# cpu.net
KiCad netlist of a schematic drawn in Altium Designer
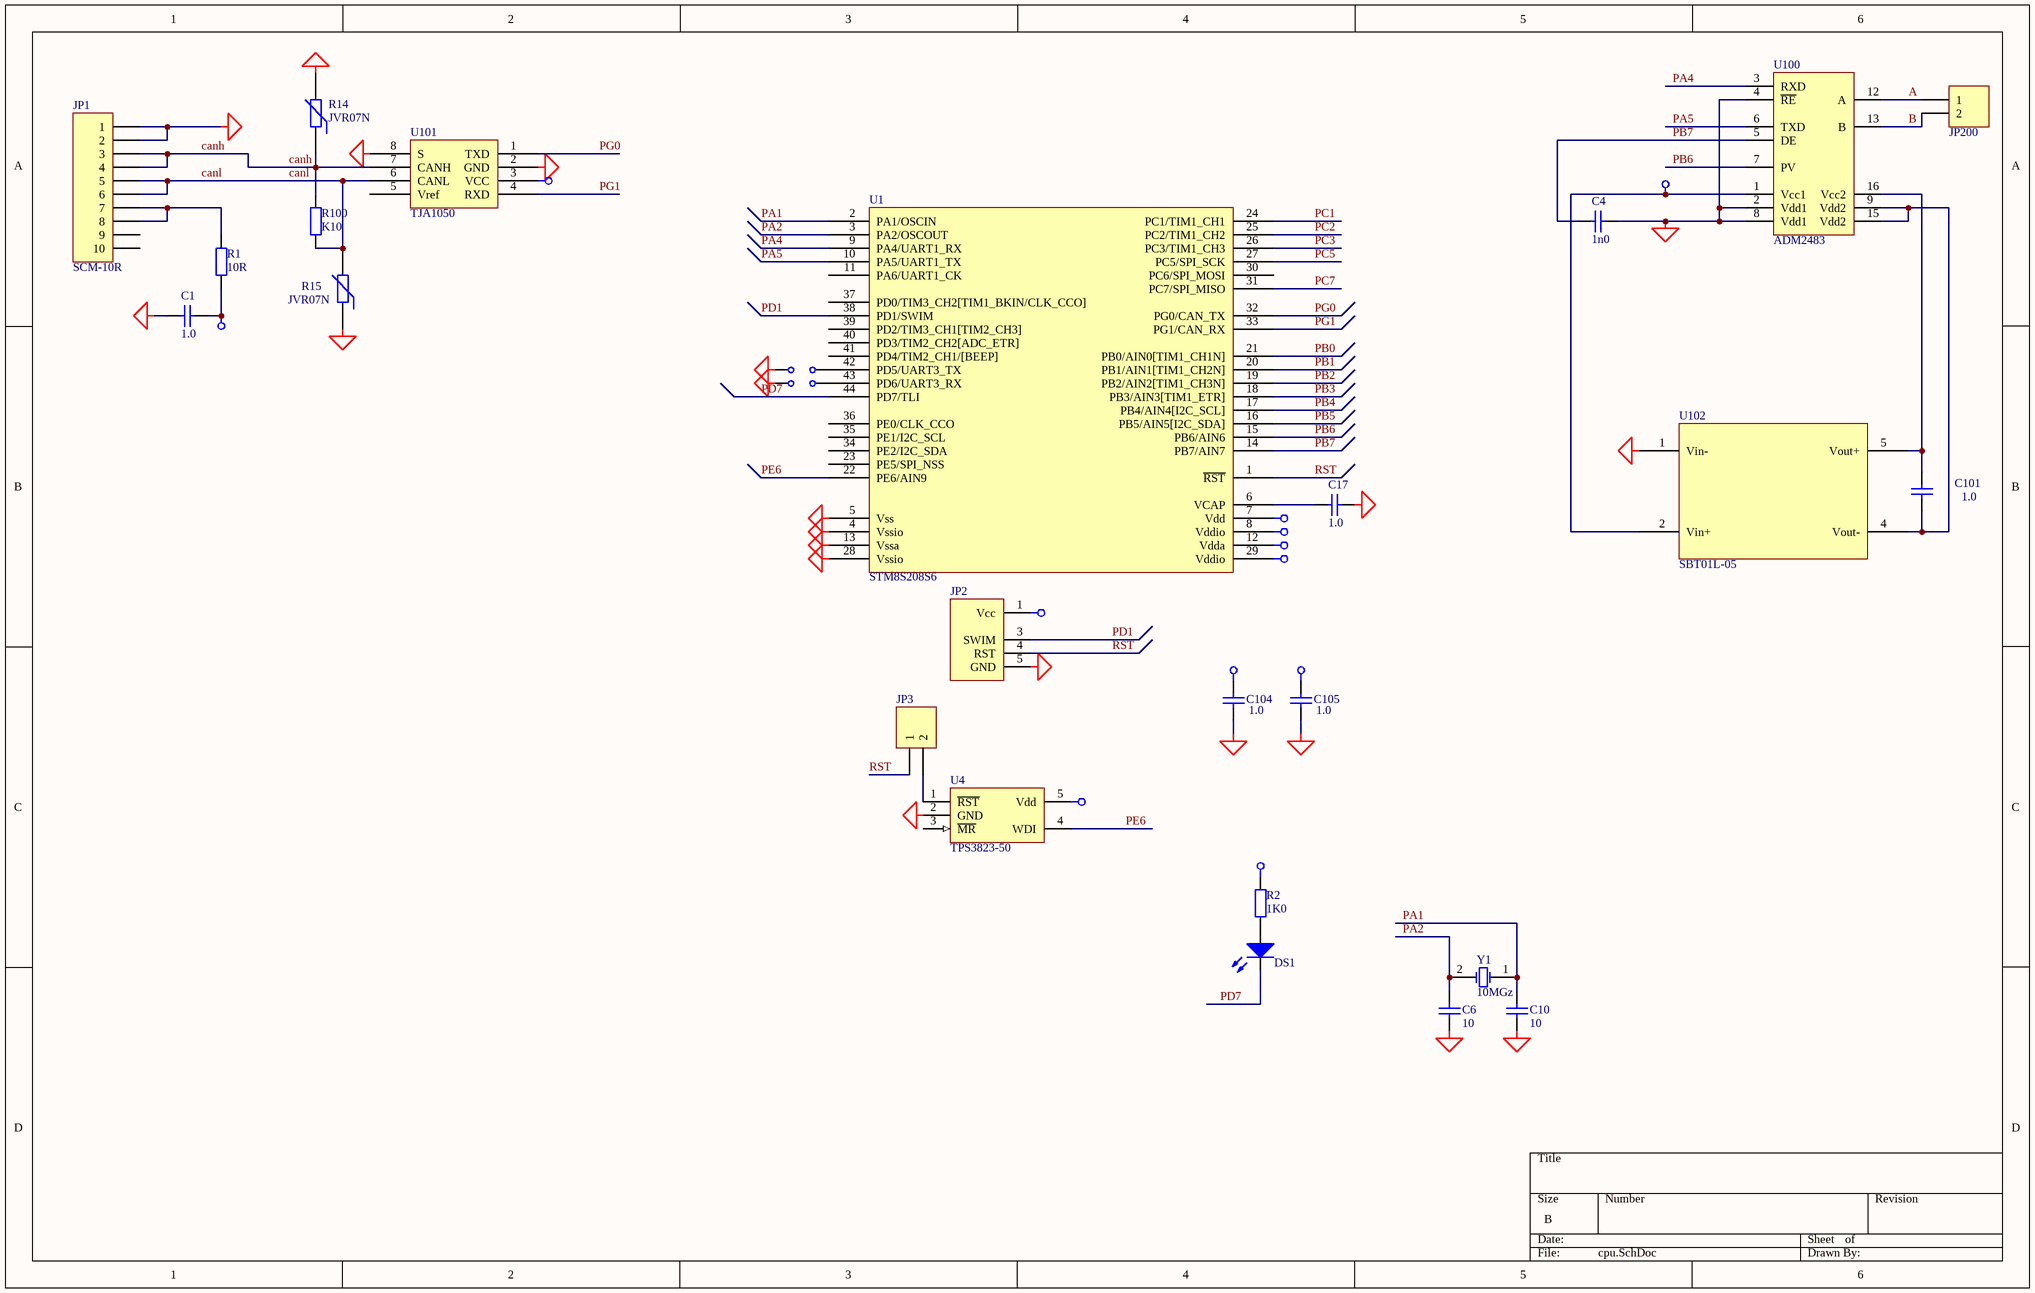
[diagram p0: cpu.SchDoc]

(export (version "E")
  (design (tool "Eeschema 10.0.6"))
  (components
    (comp (ref "C1")
      (value "1.0")
      (footprint "_1206")
      (description "Capacitor")
      (fields (field (name "MANUFACTURER") "Generic Components") (field (name "PUBLISHER") "Altium Limited"))
      (libsource (lib "BUF") (part "Cap"))
    )
    (comp (ref "C4")
      (value "1n0")
      (footprint "_1206")
      (description "Capacitor (Semiconductor SIM Model)")
      (fields (field (name "MANUFACTURER") "Generic Components") (field (name "PUBLISHER") "Altium Limited"))
      (libsource (lib "Miscellaneous Devices") (part "Cap Semi"))
    )
    (comp (ref "C6")
      (value "10")
      (footprint "_1206")
      (description "Capacitor (Semiconductor SIM Model)")
      (fields (field (name "MANUFACTURER") "Generic Components") (field (name "PUBLISHER") "Altium Limited"))
      (libsource (lib "Miscellaneous Devices") (part "Cap Semi"))
    )
    (comp (ref "C10")
      (value "10")
      (footprint "_1206")
      (description "Capacitor (Semiconductor SIM Model)")
      (fields (field (name "MANUFACTURER") "Generic Components") (field (name "PUBLISHER") "Altium Limited"))
      (libsource (lib "Miscellaneous Devices") (part "Cap Semi"))
    )
    (comp (ref "C17")
      (value "1.0")
      (footprint "_1206")
      (description "Capacitor (Semiconductor SIM Model)")
      (fields (field (name "MANUFACTURER") "Generic Components") (field (name "PUBLISHER") "Altium Limited"))
      (libsource (lib "Miscellaneous Devices") (part "Cap Semi"))
    )
    (comp (ref "C101")
      (value "1.0")
      (footprint "_1206")
      (description "Capacitor (Semiconductor SIM Model)")
      (fields (field (name "MANUFACTURER") "Generic Components") (field (name "PUBLISHER") "Altium Limited"))
      (libsource (lib "Miscellaneous Devices") (part "Cap Semi"))
    )
    (comp (ref "C104")
      (value "1.0")
      (footprint "_1206")
      (description "Capacitor")
      (fields (field (name "MANUFACTURER") "Generic Components") (field (name "PUBLISHER") "Altium Limited"))
      (libsource (lib "BUF") (part "Cap"))
    )
    (comp (ref "C105")
      (value "1.0")
      (footprint "_1206")
      (description "Capacitor")
      (fields (field (name "MANUFACTURER") "Generic Components") (field (name "PUBLISHER") "Altium Limited"))
      (libsource (lib "BUF") (part "Cap"))
    )
    (comp (ref "DS1")
      (value "LED0")
      (footprint "el3")
      (description "Typical INFRARED GaAs LED")
      (fields (field (name "MANUFACTURER") "Generic Components") (field (name "PUBLISHER") "Altium Limited"))
      (libsource (lib "PAL") (part "LED0"))
    )
    (comp (ref "J1")
      (value "PLS2")
      (footprint "jmp")
      (description "Switch")
      (fields (field (name "MANUFACTURER") "Generic Components") (field (name "PUBLISHER") "Altium Limited"))
      (libsource (lib "PAL") (part "JMP"))
    )
    (comp (ref "J2")
      (value "PLS2")
      (footprint "jmp")
      (description "Switch")
      (fields (field (name "MANUFACTURER") "Generic Components") (field (name "PUBLISHER") "Altium Limited"))
      (libsource (lib "PAL") (part "JMP"))
    )
    (comp (ref "JP1")
      (value "SCM-10R")
      (footprint "HDR2X5")
      (description "Header, 10-Pin")
      (fields (field (name "MANUFACTURER") "Generic Components") (field (name "PUBLISHER") "Altium Limited"))
      (libsource (lib "Miscellaneous Connectors") (part "MHDR1X10"))
    )
    (comp (ref "JP2") (value "~") (footprint "HDR1X5_uart") (libsource (lib "PAL") (part "SWIM_CONN")))
    (comp (ref "JP3")
      (value "~")
      (footprint "HDR1X2")
      (description "Header, 2-Pin")
      (fields (field (name "MANUFACTURER") "Generic Components") (field (name "PUBLISHER") "Altium Limited"))
      (libsource (lib "Miscellaneous Connectors") (part "Header 2"))
    )
    (comp (ref "JP200")
      (value "15EDGR-3.5-2P")
      (footprint "2EDGR-3.5-2P")
      (description "Header, 2-Pin")
      (fields (field (name "MANUFACTURER") "Generic Components") (field (name "PUBLISHER") "Altium Limited"))
      (libsource (lib "Miscellaneous Connectors") (part "MHDR1X2"))
    )
    (comp (ref "R1")
      (value "10R")
      (footprint "_1206")
      (description "Resistor")
      (fields (field (name "MANUFACTURER") "Generic Components") (field (name "PUBLISHER") "Altium Limited"))
      (libsource (lib "Miscellaneous Devices") (part "Res2"))
    )
    (comp (ref "R2")
      (value "1K0")
      (footprint "_1206")
      (description "Resistor")
      (fields (field (name "MANUFACTURER") "Generic Components") (field (name "PUBLISHER") "Altium Limited"))
      (libsource (lib "") (part "Res2_1"))
    )
    (comp (ref "R14")
      (value "JVR07N")
      (footprint "JVR07N")
      (description "Varistor (Voltage-Sensitive Resistor)")
      (fields (field (name "MANUFACTURER") "Generic Components") (field (name "PUBLISHER") "Altium Limited"))
      (libsource (lib "Miscellaneous Devices") (part "Res Varistor"))
    )
    (comp (ref "R15")
      (value "JVR07N")
      (footprint "JVR07N")
      (description "Varistor (Voltage-Sensitive Resistor)")
      (fields (field (name "MANUFACTURER") "Generic Components") (field (name "PUBLISHER") "Altium Limited"))
      (libsource (lib "Miscellaneous Devices") (part "Res Varistor"))
    )
    (comp (ref "R100")
      (value "K10")
      (footprint "_1206")
      (description "Resistor")
      (fields (field (name "MANUFACTURER") "Generic Components") (field (name "PUBLISHER") "Altium Limited"))
      (libsource (lib "Miscellaneous Devices") (part "Res2"))
    )
    (comp (ref "U1")
      (value "STM8S208S6")
      (footprint "QFP10X10-G44/G10N")
      (libsource (lib "PAL") (part "STM8S208S6"))
    )
    (comp (ref "U4")
      (value "TPS3823-50")
      (footprint "SO-G5/P.95")
      (description "Reset IC")
      (fields
        (field (name "MANUFACTURER") "National Semiconductor")
        (field (name "PUBLISHER") "Altium Limited")
      )
      (libsource (lib "PAL") (part "TPS3823"))
    )
    (comp (ref "U100") (value "ADM2483") (footprint "SO-G16/D10.4") (libsource (lib "PAL") (part "ADM2483")))
    (comp (ref "U101") (value "TJA1050") (footprint "SO-G8/D5") (libsource (lib "PAL") (part "TJA1050")))
    (comp (ref "U102") (value "SBT01L-05") (footprint "SBT01L") (libsource (lib "PAL") (part "SBT01L")))
    (comp (ref "Y1")
      (value "10MGz")
      (footprint "QWARZ1")
      (description "Crystal Oscillator")
      (fields (field (name "MANUFACTURER") "Generic Components") (field (name "PUBLISHER") "Altium Limited"))
      (libsource (lib "Miscellaneous Devices") (part "XTAL"))
    )
  )
  (nets
    (net (code "1") (name "+5v") (class "Default")
      (node (ref "C1") (pin "2") (pinfunction "2_2") (pintype "passive"))
      (node (ref "C104") (pin "2") (pinfunction "2_2") (pintype "passive"))
      (node (ref "C105") (pin "2") (pinfunction "2_2") (pintype "passive"))
      (node (ref "JP2") (pin "1") (pinfunction "Vcc_1") (pintype "passive"))
      (node (ref "R1") (pin "1") (pinfunction "1_1") (pintype "passive"))
      (node (ref "R2") (pin "1") (pinfunction "1_1") (pintype "passive"))
      (node (ref "U1") (pin "29") (pinfunction "Vddio_29") (pintype "passive"))
      (node (ref "U1") (pin "7") (pinfunction "Vdd_7") (pintype "passive"))
      (node (ref "U1") (pin "8") (pinfunction "Vddio_8") (pintype "passive"))
      (node (ref "U100") (pin "1") (pinfunction "Vcc1_1") (pintype "passive"))
      (node (ref "U101") (pin "3") (pinfunction "VCC_3") (pintype "passive"))
      (node (ref "U102") (pin "2") (pinfunction "Vin+_2") (pintype "passive"))
      (node (ref "U4") (pin "5") (pinfunction "Vdd_5") (pintype "power_in"))
    )
    (net (code "2") (name "/A") (class "Default")
      (node (ref "JP200") (pin "1") (pinfunction "1_1") (pintype "passive"))
      (node (ref "U100") (pin "12") (pinfunction "A_12") (pintype "passive"))
    )
    (net (code "3") (name "/B") (class "Default")
      (node (ref "JP200") (pin "2") (pinfunction "2_2") (pintype "passive"))
      (node (ref "U100") (pin "13") (pinfunction "B_13") (pintype "passive"))
    )
    (net (code "4") (name "/PA1") (class "Default")
      (node (ref "C10") (pin "2") (pinfunction "2_2") (pintype "passive"))
      (node (ref "U1") (pin "2") (pinfunction "PA1/OSCIN_2") (pintype "passive"))
      (node (ref "Y1") (pin "1") (pinfunction "OSC1_1") (pintype "passive"))
    )
    (net (code "5") (name "/PA2") (class "Default")
      (node (ref "C6") (pin "2") (pinfunction "2_2") (pintype "passive"))
      (node (ref "U1") (pin "3") (pinfunction "PA2/OSCOUT_3") (pintype "passive"))
      (node (ref "Y1") (pin "2") (pinfunction "OSC2_2") (pintype "passive"))
    )
    (net (code "6") (name "/PA4") (class "Default")
      (node (ref "U1") (pin "9") (pinfunction "PA4/UART1_RX_9") (pintype "passive"))
      (node (ref "U100") (pin "3") (pinfunction "RXD_3") (pintype "passive"))
    )
    (net (code "7") (name "/PA5") (class "Default")
      (node (ref "U1") (pin "10") (pinfunction "PA5/UART1_TX_10") (pintype "passive"))
      (node (ref "U100") (pin "6") (pinfunction "TXD_6") (pintype "passive"))
    )
    (net (code "8") (name "/PB0") (class "Default")
      (node (ref "U1") (pin "21") (pinfunction "PB0/AIN0[TIM1_CH1N]_21") (pintype "passive"))
    )
    (net (code "9") (name "/PB1") (class "Default")
      (node (ref "U1") (pin "20") (pinfunction "PB1/AIN1[TIM1_CH2N]_20") (pintype "passive"))
    )
    (net (code "10") (name "/PB2") (class "Default")
      (node (ref "U1") (pin "19") (pinfunction "PB2/AIN2[TIM1_CH3N]_19") (pintype "passive"))
    )
    (net (code "11") (name "/PB3") (class "Default")
      (node (ref "U1") (pin "18") (pinfunction "PB3/AIN3[TIM1_ETR]_18") (pintype "passive"))
    )
    (net (code "12") (name "/PB4") (class "Default")
      (node (ref "U1") (pin "17") (pinfunction "PB4/AIN4[I2C_SCL]_17") (pintype "passive"))
    )
    (net (code "13") (name "/PB5") (class "Default")
      (node (ref "U1") (pin "16") (pinfunction "PB5/AIN5[I2C_SDA]_16") (pintype "passive"))
    )
    (net (code "14") (name "/PB6") (class "Default")
      (node (ref "U1") (pin "15") (pinfunction "PB6/AIN6_15") (pintype "passive"))
      (node (ref "U100") (pin "7") (pinfunction "PV_7") (pintype "passive"))
    )
    (net (code "15") (name "/PB7") (class "Default")
      (node (ref "C4") (pin "1") (pinfunction "1_1") (pintype "passive"))
      (node (ref "U1") (pin "14") (pinfunction "PB7/AIN7_14") (pintype "passive"))
      (node (ref "U100") (pin "5") (pinfunction "DE_5") (pintype "passive"))
    )
    (net (code "16") (name "/PC1") (class "Default")
      (node (ref "U1") (pin "24") (pinfunction "PC1/TIM1_CH1_24") (pintype "passive"))
    )
    (net (code "17") (name "/PC2") (class "Default")
      (node (ref "U1") (pin "25") (pinfunction "PC2/TIM1_CH2_25") (pintype "passive"))
    )
    (net (code "18") (name "/PC3") (class "Default")
      (node (ref "U1") (pin "26") (pinfunction "PC3/TIM1_CH3_26") (pintype "passive"))
    )
    (net (code "19") (name "/PC5") (class "Default")
      (node (ref "U1") (pin "27") (pinfunction "PC5/SPI_SCK_27") (pintype "passive"))
    )
    (net (code "20") (name "/PC7") (class "Default")
      (node (ref "U1") (pin "31") (pinfunction "PC7/SPI_MISO_31") (pintype "passive"))
    )
    (net (code "21") (name "/PD1") (class "Default")
      (node (ref "JP2") (pin "3") (pinfunction "SWIM_3") (pintype "passive"))
      (node (ref "U1") (pin "38") (pinfunction "PD1/SWIM_38") (pintype "passive"))
    )
    (net (code "22") (name "/PD7") (class "Default")
      (node (ref "DS1") (pin "2") (pinfunction "K_2") (pintype "passive"))
      (node (ref "U1") (pin "44") (pinfunction "PD7/TLI_44") (pintype "passive"))
    )
    (net (code "23") (name "/PE6") (class "Default")
      (node (ref "U1") (pin "22") (pinfunction "PE6/AIN9_22") (pintype "passive"))
      (node (ref "U4") (pin "4") (pinfunction "WDI_4") (pintype "passive"))
    )
    (net (code "24") (name "/PG0") (class "Default")
      (node (ref "U1") (pin "32") (pinfunction "PG0/CAN_TX_32") (pintype "passive"))
      (node (ref "U101") (pin "1") (pinfunction "TXD_1") (pintype "passive"))
    )
    (net (code "25") (name "/PG1") (class "Default")
      (node (ref "U1") (pin "33") (pinfunction "PG1/CAN_RX_33") (pintype "passive"))
      (node (ref "U101") (pin "4") (pinfunction "RXD_4") (pintype "passive"))
    )
    (net (code "26") (name "/RST") (class "Default")
      (node (ref "JP2") (pin "4") (pinfunction "RST_4") (pintype "passive"))
      (node (ref "JP3") (pin "1") (pinfunction "1_1") (pintype "passive"))
      (node (ref "U1") (pin "1") (pinfunction "~{RST}_1") (pintype "passive"))
    )
    (net (code "27") (name "/canh") (class "Default")
      (node (ref "JP1") (pin "3") (pinfunction "3_3") (pintype "passive"))
      (node (ref "JP1") (pin "4") (pinfunction "4_4") (pintype "passive"))
      (node (ref "R100") (pin "2") (pinfunction "2_2") (pintype "passive"))
      (node (ref "R14") (pin "1") (pinfunction "1_1") (pintype "passive"))
      (node (ref "U101") (pin "7") (pinfunction "CANH_7") (pintype "passive"))
    )
    (net (code "28") (name "/canl") (class "Default")
      (node (ref "JP1") (pin "5") (pinfunction "5_5") (pintype "passive"))
      (node (ref "JP1") (pin "6") (pinfunction "6_6") (pintype "passive"))
      (node (ref "R100") (pin "1") (pinfunction "1_1") (pintype "passive"))
      (node (ref "R15") (pin "2") (pinfunction "2_2") (pintype "passive"))
      (node (ref "U101") (pin "6") (pinfunction "CANL_6") (pintype "passive"))
    )
    (net (code "29") (name "GND") (class "Default")
      (node (ref "C1") (pin "1") (pinfunction "1_1") (pintype "passive"))
      (node (ref "C10") (pin "1") (pinfunction "1_1") (pintype "passive"))
      (node (ref "C104") (pin "1") (pinfunction "1_1") (pintype "passive"))
      (node (ref "C105") (pin "1") (pinfunction "1_1") (pintype "passive"))
      (node (ref "C17") (pin "1") (pinfunction "1_1") (pintype "passive"))
      (node (ref "C4") (pin "2") (pinfunction "2_2") (pintype "passive"))
      (node (ref "C6") (pin "1") (pinfunction "1_1") (pintype "passive"))
      (node (ref "J1") (pin "1") (pinfunction "1_1") (pintype "passive"))
      (node (ref "J2") (pin "1") (pinfunction "1_1") (pintype "passive"))
      (node (ref "JP1") (pin "1") (pinfunction "1_1") (pintype "passive"))
      (node (ref "JP1") (pin "2") (pinfunction "2_2") (pintype "passive"))
      (node (ref "JP2") (pin "5") (pinfunction "GND_5") (pintype "passive"))
      (node (ref "R14") (pin "2") (pinfunction "2_2") (pintype "passive"))
      (node (ref "R15") (pin "1") (pinfunction "1_1") (pintype "passive"))
      (node (ref "U1") (pin "13") (pinfunction "Vssa_13") (pintype "passive"))
      (node (ref "U1") (pin "28") (pinfunction "Vssio_28") (pintype "passive"))
      (node (ref "U1") (pin "4") (pinfunction "Vssio_4") (pintype "passive"))
      (node (ref "U1") (pin "5") (pinfunction "Vss_5") (pintype "passive"))
      (node (ref "U100") (pin "2") (pinfunction "Vdd1_2") (pintype "passive"))
      (node (ref "U100") (pin "4") (pinfunction "~{RE}_4") (pintype "passive"))
      (node (ref "U100") (pin "8") (pinfunction "Vdd1_8") (pintype "passive"))
      (node (ref "U101") (pin "2") (pinfunction "GND_2") (pintype "passive"))
      (node (ref "U101") (pin "8") (pinfunction "S_8") (pintype "passive"))
      (node (ref "U102") (pin "1") (pinfunction "Vin-_1") (pintype "passive"))
      (node (ref "U4") (pin "2") (pinfunction "GND_2") (pintype "power_in"))
    )
    (net (code "30") (name "Net-(DS1-A)") (class "Default")
      (node (ref "DS1") (pin "1") (pinfunction "A_1") (pintype "passive"))
      (node (ref "R2") (pin "2") (pinfunction "2_2") (pintype "passive"))
    )
    (net (code "31") (name "Net-(JP1-Pad7)") (class "Default")
      (node (ref "JP1") (pin "7") (pinfunction "7_7") (pintype "passive"))
      (node (ref "JP1") (pin "8") (pinfunction "8_8") (pintype "passive"))
      (node (ref "R1") (pin "2") (pinfunction "2_2") (pintype "passive"))
    )
    (net (code "32") (name "Net-(U1-PD5{slash}UART3_TX)") (class "Default")
      (node (ref "J2") (pin "2") (pinfunction "2_2") (pintype "passive"))
      (node (ref "U1") (pin "42") (pinfunction "PD5/UART3_TX_42") (pintype "passive"))
    )
    (net (code "33") (name "Net-(U1-PD6{slash}UART3_RX)") (class "Default")
      (node (ref "J1") (pin "2") (pinfunction "2_2") (pintype "passive"))
      (node (ref "U1") (pin "43") (pinfunction "PD6/UART3_RX_43") (pintype "passive"))
    )
    (net (code "34") (name "Net-(U1-VCAP)") (class "Default")
      (node (ref "C17") (pin "2") (pinfunction "2_2") (pintype "passive"))
      (node (ref "U1") (pin "6") (pinfunction "VCAP_6") (pintype "passive"))
    )
    (net (code "35") (name "Net-(U4-~{RST})") (class "Default")
      (node (ref "JP3") (pin "2") (pinfunction "2_2") (pintype "passive"))
      (node (ref "U4") (pin "1") (pinfunction "~{RST}_1") (pintype "power_in"))
    )
    (net (code "36") (name "Net-(U100-Vcc2)") (class "Default")
      (node (ref "C101") (pin "2") (pinfunction "2_2") (pintype "passive"))
      (node (ref "U100") (pin "16") (pinfunction "Vcc2_16") (pintype "passive"))
      (node (ref "U102") (pin "5") (pinfunction "Vout+_5") (pintype "passive"))
    )
    (net (code "37") (name "Net-(U102-Vout-)") (class "Default")
      (node (ref "C101") (pin "1") (pinfunction "1_1") (pintype "passive"))
      (node (ref "U100") (pin "15") (pinfunction "Vdd2_15") (pintype "passive"))
      (node (ref "U100") (pin "9") (pinfunction "Vdd2_9") (pintype "passive"))
      (node (ref "U102") (pin "4") (pinfunction "Vout-_4") (pintype "passive"))
    )
    (net (code "38") (name "Uref") (class "Default")
      (node (ref "U1") (pin "12") (pinfunction "Vdda_12") (pintype "passive"))
    )
    (net (code "39") (name "unconnected-(JP1-Pad9)") (class "Default")
      (node (ref "JP1") (pin "9") (pinfunction "9_9") (pintype "passive"))
    )
    (net (code "40") (name "unconnected-(JP1-Pad10)") (class "Default")
      (node (ref "JP1") (pin "10") (pinfunction "10_10") (pintype "passive"))
    )
    (net (code "41") (name "unconnected-(U1-PA6{slash}UART1_CK-Pad11)") (class "Default")
      (node (ref "U1") (pin "11") (pinfunction "PA6/UART1_CK_11") (pintype "passive"))
    )
    (net (code "42") (name "unconnected-(U1-PC6{slash}SPI_MOSI-Pad30)") (class "Default")
      (node (ref "U1") (pin "30") (pinfunction "PC6/SPI_MOSI_30") (pintype "passive"))
    )
    (net (code "43") (name "unconnected-(U1-PD0{slash}TIM3_CH2[TIM1_BKIN{slash}CLK_CCO]-Pad37)") (class "Default")
      (node (ref "U1") (pin "37") (pinfunction "PD0/TIM3_CH2[TIM1_BKIN/CLK_CCO]_37") (pintype "passive"))
    )
    (net (code "44") (name "unconnected-(U1-PD2{slash}TIM3_CH1[TIM2_CH3]-Pad39)") (class "Default")
      (node (ref "U1") (pin "39") (pinfunction "PD2/TIM3_CH1[TIM2_CH3]_39") (pintype "passive"))
    )
    (net (code "45") (name "unconnected-(U1-PD3{slash}TIM2_CH2[ADC_ETR]-Pad40)") (class "Default")
      (node (ref "U1") (pin "40") (pinfunction "PD3/TIM2_CH2[ADC_ETR]_40") (pintype "passive"))
    )
    (net (code "46") (name "unconnected-(U1-PD4{slash}TIM2_CH1{slash}[BEEP]-Pad41)") (class "Default")
      (node (ref "U1") (pin "41") (pinfunction "PD4/TIM2_CH1/[BEEP]_41") (pintype "passive"))
    )
    (net (code "47") (name "unconnected-(U1-PE0{slash}CLK_CCO-Pad36)") (class "Default")
      (node (ref "U1") (pin "36") (pinfunction "PE0/CLK_CCO_36") (pintype "passive"))
    )
    (net (code "48") (name "unconnected-(U1-PE1{slash}I2C_SCL-Pad35)") (class "Default")
      (node (ref "U1") (pin "35") (pinfunction "PE1/I2C_SCL_35") (pintype "passive"))
    )
    (net (code "49") (name "unconnected-(U1-PE2{slash}I2C_SDA-Pad34)") (class "Default")
      (node (ref "U1") (pin "34") (pinfunction "PE2/I2C_SDA_34") (pintype "passive"))
    )
    (net (code "50") (name "unconnected-(U1-PE5{slash}SPI_NSS-Pad23)") (class "Default")
      (node (ref "U1") (pin "23") (pinfunction "PE5/SPI_NSS_23") (pintype "passive"))
    )
    (net (code "51") (name "unconnected-(U4-~{MR}-Pad3)") (class "Default")
      (node (ref "U4") (pin "3") (pinfunction "~{MR}_3") (pintype "input"))
    )
    (net (code "52") (name "unconnected-(U101-Vref-Pad5)") (class "Default")
      (node (ref "U101") (pin "5") (pinfunction "Vref_5") (pintype "passive"))
    )
  )
)
